# Power.net
KiCad netlist of a schematic drawn in Altium Designer
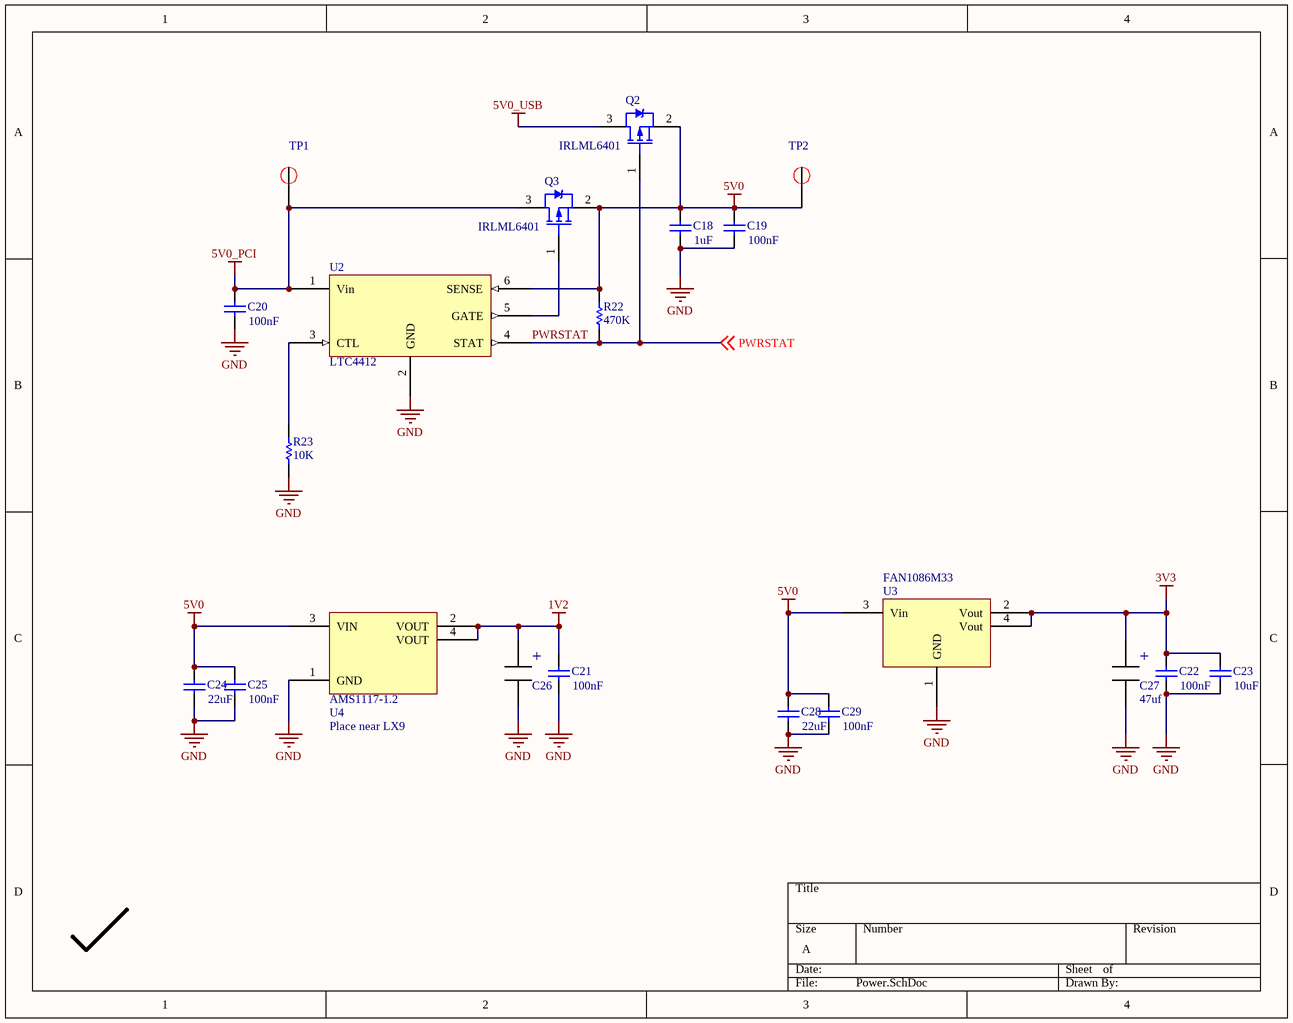
[diagram p0: Power.SchDoc]

(export (version "E")
  (design (tool "Eeschema 10.0.6"))
  (components
    (comp (ref "C18")
      (value "1uF")
      (footprint "0603PKG")
      (description "Capacitor")
      (fields (field (name "Comment") "Cap") (field (name "PUBLISHER") "Altium Limited"))
      (libsource (lib "Miscellaneous Devices") (part "Cap"))
    )
    (comp (ref "C19")
      (value "100nF")
      (footprint "0603PKG")
      (description "Capacitor")
      (fields (field (name "Comment") "Cap") (field (name "PUBLISHER") "Altium Limited"))
      (libsource (lib "Miscellaneous Devices") (part "Cap"))
    )
    (comp (ref "C20")
      (value "100nF")
      (footprint "0603PKG")
      (description "Capacitor")
      (fields (field (name "Comment") "Cap") (field (name "PUBLISHER") "Altium Limited"))
      (libsource (lib "Miscellaneous Devices") (part "Cap"))
    )
    (comp (ref "C21")
      (value "100nF")
      (footprint "C0805")
      (description "Capacitor")
      (fields (field (name "Comment") "Cap") (field (name "PUBLISHER") "Altium Limited"))
      (libsource (lib "Miscellaneous Devices") (part "Cap"))
    )
    (comp (ref "C22")
      (value "100nF")
      (footprint "C0805")
      (description "Capacitor")
      (fields (field (name "Comment") "Cap") (field (name "PUBLISHER") "Altium Limited"))
      (libsource (lib "Miscellaneous Devices") (part "Cap"))
    )
    (comp (ref "C23")
      (value "10uF")
      (footprint "C0805")
      (description "Capacitor")
      (fields (field (name "Comment") "Cap") (field (name "PUBLISHER") "Altium Limited"))
      (libsource (lib "Miscellaneous Devices") (part "Cap"))
    )
    (comp (ref "C24")
      (value "22uF")
      (footprint "C1206")
      (description "Capacitor")
      (fields (field (name "Comment") "Cap") (field (name "PUBLISHER") "Altium Limited"))
      (libsource (lib "Miscellaneous Devices") (part "Cap"))
    )
    (comp (ref "C25")
      (value "100nF")
      (footprint "C0805")
      (description "Capacitor")
      (fields (field (name "Comment") "Cap") (field (name "PUBLISHER") "Altium Limited"))
      (libsource (lib "Miscellaneous Devices") (part "Cap"))
    )
    (comp (ref "C26")
      (value "Capacitor")
      (footprint "Capacitor")
      (libsource (lib "Integrated_Library") (part "SMS capacitor"))
    )
    (comp (ref "C27")
      (value "47uf")
      (footprint "Capacitor")
      (fields (field (name "Comment") "Capacitor"))
      (libsource (lib "Integrated_Library") (part "SMS capacitor"))
    )
    (comp (ref "C28")
      (value "22uF")
      (footprint "C1206")
      (description "Capacitor")
      (fields (field (name "Comment") "Cap") (field (name "PUBLISHER") "Altium Limited"))
      (libsource (lib "Miscellaneous Devices") (part "Cap"))
    )
    (comp (ref "C29")
      (value "100nF")
      (footprint "C0805")
      (description "Capacitor")
      (fields (field (name "Comment") "Cap") (field (name "PUBLISHER") "Altium Limited"))
      (libsource (lib "Miscellaneous Devices") (part "Cap"))
    )
    (comp (ref "Q2")
      (value "IRLML6401")
      (footprint "SOT23")
      (description "P-Channel Power MOSFET")
      (fields (field (name "PUBLISHER") "Altium Limited"))
      (libsource (lib "Miscellaneous Devices") (part "PMOS-2"))
    )
    (comp (ref "Q3")
      (value "IRLML6401")
      (footprint "SOT23")
      (description "P-Channel Power MOSFET")
      (fields (field (name "PUBLISHER") "Altium Limited"))
      (libsource (lib "Miscellaneous Devices") (part "PMOS-2"))
    )
    (comp (ref "R22")
      (value "470K")
      (footprint "0603PKG")
      (description "Semiconductor Resistor")
      (fields (field (name "Comment") "Res Semi") (field (name "PUBLISHER") "Altium Limited"))
      (libsource (lib "Miscellaneous Devices") (part "Res Semi"))
    )
    (comp (ref "R23")
      (value "10K")
      (footprint "0603PKG")
      (description "Semiconductor Resistor")
      (fields (field (name "Comment") "Res Semi") (field (name "PUBLISHER") "Altium Limited"))
      (libsource (lib "Miscellaneous Devices") (part "Res Semi"))
    )
    (comp (ref "TP1")
      (value "TP")
      (footprint "TP_15")
      (libsource (lib "Connector_IntLib") (part "Test Point"))
    )
    (comp (ref "TP2")
      (value "TP")
      (footprint "TP_15")
      (libsource (lib "Connector_IntLib") (part "Test Point"))
    )
    (comp (ref "U2")
      (value "LTC4412")
      (footprint "SOT23-6")
      (description "Low Loss PowerPath™  Controller in ThinSOT")
      (libsource (lib "Connector_IntLib") (part "LTC4412"))
    )
    (comp (ref "U3")
      (value "FAN1086M33")
      (footprint "TO263")
      (libsource (lib "Connector_IntLib") (part "FAN1086M33"))
    )
    (comp (ref "U4")
      (value "AMS1117-1.2")
      (footprint "SOT223")
      (description "1A Adjustable/Fixed Low Dropout Linear Regulator")
      (libsource (lib "Conn_Schlib") (part "AMS1117-1.2"))
    )
  )
  (nets
    (net (code "1") (name "1V2") (class "Default")
      (node (ref "C21") (pin "2") (pinfunction "2_2") (pintype "passive"))
      (node (ref "C26") (pin "2") (pintype "power_in"))
      (node (ref "U4") (pin "2") (pinfunction "VOUT_2") (pintype "power_in"))
      (node (ref "U4") (pin "4") (pinfunction "VOUT_4") (pintype "power_in"))
    )
    (net (code "2") (name "3V3") (class "Default")
      (node (ref "C22") (pin "2") (pinfunction "2_2") (pintype "passive"))
      (node (ref "C23") (pin "2") (pinfunction "2_2") (pintype "passive"))
      (node (ref "C27") (pin "2") (pintype "power_in"))
      (node (ref "U3") (pin "2") (pinfunction "Vout_2") (pintype "power_in"))
      (node (ref "U3") (pin "4") (pinfunction "Vout_4") (pintype "power_in"))
    )
    (net (code "3") (name "5V0") (class "Default")
      (node (ref "C18") (pin "2") (pinfunction "2_2") (pintype "passive"))
      (node (ref "C19") (pin "2") (pinfunction "2_2") (pintype "passive"))
      (node (ref "C24") (pin "2") (pinfunction "2_2") (pintype "passive"))
      (node (ref "C25") (pin "2") (pinfunction "2_2") (pintype "passive"))
      (node (ref "C28") (pin "2") (pinfunction "2_2") (pintype "passive"))
      (node (ref "C29") (pin "2") (pinfunction "2_2") (pintype "passive"))
      (node (ref "Q2") (pin "2") (pinfunction "S_2") (pintype "passive"))
      (node (ref "Q3") (pin "2") (pinfunction "S_2") (pintype "passive"))
      (node (ref "R22") (pin "2") (pinfunction "2_2") (pintype "passive"))
      (node (ref "TP2") (pin "1") (pinfunction "1_1") (pintype "passive"))
      (node (ref "U2") (pin "6") (pinfunction "SENSE_6") (pintype "input"))
      (node (ref "U3") (pin "3") (pinfunction "Vin_3") (pintype "power_in"))
      (node (ref "U4") (pin "3") (pinfunction "VIN_3") (pintype "power_in"))
    )
    (net (code "4") (name "5V0_PCI") (class "Default")
      (node (ref "C20") (pin "2") (pinfunction "2_2") (pintype "passive"))
      (node (ref "Q3") (pin "3") (pinfunction "D_3") (pintype "passive"))
      (node (ref "TP1") (pin "1") (pinfunction "1_1") (pintype "passive"))
      (node (ref "U2") (pin "1") (pinfunction "Vin_1") (pintype "power_in"))
    )
    (net (code "5") (name "5V0_USB") (class "Default")
      (node (ref "Q2") (pin "3") (pinfunction "D_3") (pintype "passive"))
    )
    (net (code "6") (name "GND") (class "Default")
      (node (ref "C18") (pin "1") (pinfunction "1_1") (pintype "passive"))
      (node (ref "C19") (pin "1") (pinfunction "1_1") (pintype "passive"))
      (node (ref "C20") (pin "1") (pinfunction "1_1") (pintype "passive"))
      (node (ref "C21") (pin "1") (pinfunction "1_1") (pintype "passive"))
      (node (ref "C22") (pin "1") (pinfunction "1_1") (pintype "passive"))
      (node (ref "C23") (pin "1") (pinfunction "1_1") (pintype "passive"))
      (node (ref "C24") (pin "1") (pinfunction "1_1") (pintype "passive"))
      (node (ref "C25") (pin "1") (pinfunction "1_1") (pintype "passive"))
      (node (ref "C26") (pin "1") (pintype "power_in"))
      (node (ref "C27") (pin "1") (pintype "power_in"))
      (node (ref "C28") (pin "1") (pinfunction "1_1") (pintype "passive"))
      (node (ref "C29") (pin "1") (pinfunction "1_1") (pintype "passive"))
      (node (ref "R23") (pin "1") (pinfunction "1_1") (pintype "passive"))
      (node (ref "U2") (pin "2") (pinfunction "GND_2") (pintype "power_in"))
      (node (ref "U3") (pin "1") (pinfunction "GND_1") (pintype "power_in"))
      (node (ref "U4") (pin "1") (pinfunction "GND_1") (pintype "power_in"))
    )
    (net (code "7") (name "Net-(Q3-G)") (class "Default")
      (node (ref "Q3") (pin "1") (pinfunction "G_1") (pintype "passive"))
      (node (ref "U2") (pin "5") (pinfunction "GATE_5") (pintype "output"))
    )
    (net (code "8") (name "Net-(U2-CTL)") (class "Default")
      (node (ref "R23") (pin "2") (pinfunction "2_2") (pintype "passive"))
      (node (ref "U2") (pin "3") (pinfunction "CTL_3") (pintype "input"))
    )
    (net (code "9") (name "PWRSTAT") (class "Default")
      (node (ref "Q2") (pin "1") (pinfunction "G_1") (pintype "passive"))
      (node (ref "R22") (pin "1") (pinfunction "1_1") (pintype "passive"))
      (node (ref "U2") (pin "4") (pinfunction "STAT_4") (pintype "output"))
    )
  )
)
